# sensor_board.net
KiCad netlist of a schematic drawn in EAGLE
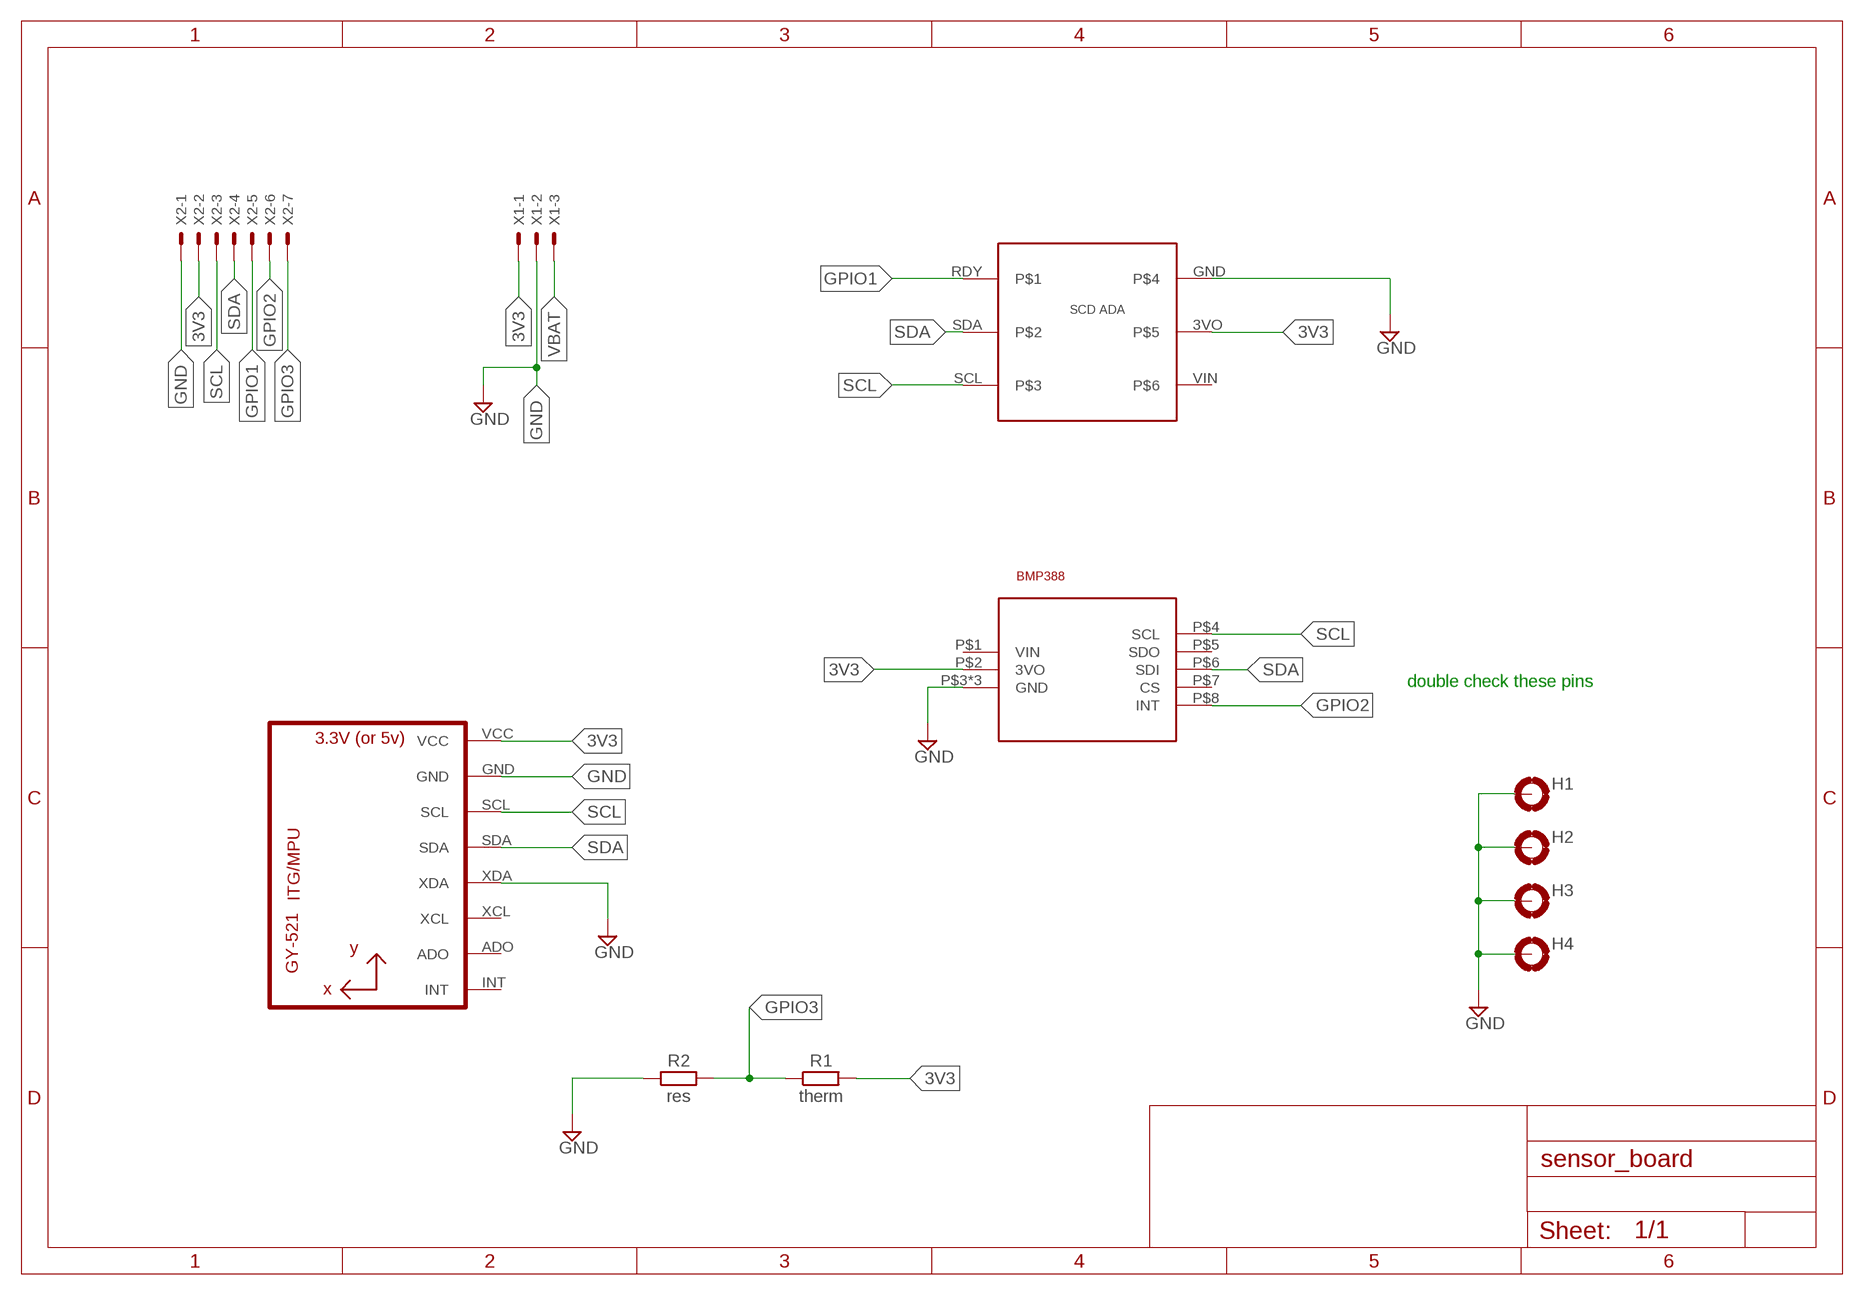
[diagram p0: schematic, sheet 1]

(export (version "E")
  (design (tool "Eeschema 10.0.6"))
  (components
    (comp (ref "H1")
      (value "MOUNT-PAD-ROUND3.0")
      (footprint "eagle-import:3,0-PAD")
      (libsource (lib "eagle-import") (part "MOUNT-PAD-ROUND3.0"))
    )
    (comp (ref "H2")
      (value "MOUNT-PAD-ROUND3.0")
      (footprint "eagle-import:3,0-PAD")
      (libsource (lib "eagle-import") (part "MOUNT-PAD-ROUND3.0"))
    )
    (comp (ref "H3")
      (value "MOUNT-PAD-ROUND3.0")
      (footprint "eagle-import:3,0-PAD")
      (libsource (lib "eagle-import") (part "MOUNT-PAD-ROUND3.0"))
    )
    (comp (ref "H4")
      (value "MOUNT-PAD-ROUND3.0")
      (footprint "eagle-import:3,0-PAD")
      (libsource (lib "eagle-import") (part "MOUNT-PAD-ROUND3.0"))
    )
    (comp (ref "R1")
      (value "therm")
      (footprint "eagle-import:RESAD1176W63L850D250B")
      (libsource (lib "eagle-import") (part "RAXIAL-11.7MM-PITCH_"))
    )
    (comp (ref "R2")
      (value "res")
      (footprint "eagle-import:RESAD1176W63L850D250B")
      (libsource (lib "eagle-import") (part "RAXIAL-11.7MM-PITCH_"))
    )
    (comp (ref "U$1")
      (value "BMP388_QT")
      (footprint "eagle-import:BMP388_QT")
      (libsource (lib "eagle-import") (part "BMP388_QT"))
    )
    (comp (ref "U$6")
      (value "SCD30_ADA")
      (footprint "eagle-import:SCD30_ADA")
      (libsource (lib "eagle-import") (part "SCD30_ADA"))
    )
    (comp (ref "U1")
      (value "GY-521MPU6050")
      (footprint "eagle-import:GY-521")
      (fields (field (name "MF") "GODREAM FORDREAM CO., LIMITED") (field (name "MP") "GY-521"))
      (libsource (lib "eagle-import") (part "GY-521MPU6050"))
    )
    (comp (ref "X1")
      (value "JST-XH-03-PIN")
      (footprint "eagle-import:JST-XH_S3B")
      (libsource (lib "eagle-import") (part "JST-XH-03-PIN"))
    )
    (comp (ref "X2")
      (value "JST-XH-07-PIN")
      (footprint "eagle-import:JST-XH_S7B")
      (libsource (lib "eagle-import") (part "JST-XH-07-PIN"))
    )
  )
  (nets
    (net (code "1") (name "3V3") (class "Default")
      (node (ref "R1") (pin "2") (pinfunction "2_2") (pintype "passive"))
      (node (ref "U$1") (pin "P$2") (pinfunction "3VO_P$2") (pintype "bidirectional"))
      (node (ref "U$6") (pin "3VO") (pinfunction "P$5_3VO") (pintype "bidirectional"))
      (node (ref "U1") (pin "VCC") (pinfunction "VCC_VCC") (pintype "bidirectional"))
      (node (ref "X1") (pin "PIN1") (pinfunction "S_PIN1") (pintype "passive"))
      (node (ref "X2") (pin "PIN2") (pinfunction "S_PIN2") (pintype "passive"))
    )
    (net (code "2") (name "GND") (class "Default")
      (node (ref "H1") (pin "B3,0") (pinfunction "MOUNT_B3,0") (pintype "passive"))
      (node (ref "H2") (pin "B3,0") (pinfunction "MOUNT_B3,0") (pintype "passive"))
      (node (ref "H3") (pin "B3,0") (pinfunction "MOUNT_B3,0") (pintype "passive"))
      (node (ref "H4") (pin "B3,0") (pinfunction "MOUNT_B3,0") (pintype "passive"))
      (node (ref "R2") (pin "1") (pinfunction "1_1") (pintype "passive"))
      (node (ref "U$1") (pin "P$10") (pinfunction "GND_P$10") (pintype "bidirectional"))
      (node (ref "U$1") (pin "P$3") (pinfunction "GND_P$3") (pintype "bidirectional"))
      (node (ref "U$1") (pin "P$9") (pinfunction "GND_P$9") (pintype "bidirectional"))
      (node (ref "U$6") (pin "GND") (pinfunction "P$4_GND") (pintype "bidirectional"))
      (node (ref "U1") (pin "GND") (pinfunction "GND_GND") (pintype "bidirectional"))
      (node (ref "U1") (pin "XDA") (pinfunction "XDA_XDA") (pintype "bidirectional"))
      (node (ref "X1") (pin "PIN2") (pinfunction "S_PIN2") (pintype "passive"))
      (node (ref "X2") (pin "PIN1") (pinfunction "S_PIN1") (pintype "passive"))
    )
    (net (code "3") (name "GPIO1") (class "Default")
      (node (ref "U$6") (pin "RDY") (pinfunction "P$1_RDY") (pintype "bidirectional"))
      (node (ref "X2") (pin "PIN5") (pinfunction "S_PIN5") (pintype "passive"))
    )
    (net (code "4") (name "GPIO2") (class "Default")
      (node (ref "U$1") (pin "P$8") (pinfunction "INT_P$8") (pintype "bidirectional"))
      (node (ref "X2") (pin "PIN6") (pinfunction "S_PIN6") (pintype "passive"))
    )
    (net (code "5") (name "GPIO3") (class "Default")
      (node (ref "R1") (pin "1") (pinfunction "1_1") (pintype "passive"))
      (node (ref "R2") (pin "2") (pinfunction "2_2") (pintype "passive"))
      (node (ref "X2") (pin "PIN7") (pinfunction "S_PIN7") (pintype "passive"))
    )
    (net (code "6") (name "SCL") (class "Default")
      (node (ref "U$1") (pin "P$4") (pinfunction "SCL_P$4") (pintype "bidirectional"))
      (node (ref "U$6") (pin "SCL") (pinfunction "P$3_SCL") (pintype "bidirectional"))
      (node (ref "U1") (pin "SCL") (pinfunction "SCL_SCL") (pintype "bidirectional"))
      (node (ref "X2") (pin "PIN3") (pinfunction "S_PIN3") (pintype "passive"))
    )
    (net (code "7") (name "SDA") (class "Default")
      (node (ref "U$1") (pin "P$6") (pinfunction "SDI_P$6") (pintype "bidirectional"))
      (node (ref "U$6") (pin "SDA") (pinfunction "P$2_SDA") (pintype "bidirectional"))
      (node (ref "U1") (pin "SDA") (pinfunction "SDA_SDA") (pintype "bidirectional"))
      (node (ref "X2") (pin "PIN4") (pinfunction "S_PIN4") (pintype "passive"))
    )
    (net (code "8") (name "VBAT") (class "Default")
      (node (ref "X1") (pin "PIN3") (pinfunction "S_PIN3") (pintype "passive"))
    )
    (net (code "9") (name "unconnected-(U$1-CS-PadP$7)") (class "Default")
      (node (ref "U$1") (pin "P$7") (pinfunction "CS_P$7") (pintype "bidirectional"))
    )
    (net (code "10") (name "unconnected-(U$1-SDO-PadP$5)") (class "Default")
      (node (ref "U$1") (pin "P$5") (pinfunction "SDO_P$5") (pintype "bidirectional"))
    )
    (net (code "11") (name "unconnected-(U$1-VIN-PadP$1)") (class "Default")
      (node (ref "U$1") (pin "P$1") (pinfunction "VIN_P$1") (pintype "bidirectional"))
    )
    (net (code "12") (name "unconnected-(U$6-P$6-PadVIN)") (class "Default")
      (node (ref "U$6") (pin "VIN") (pinfunction "P$6_VIN") (pintype "bidirectional"))
    )
    (net (code "13") (name "unconnected-(U1-PadADO)") (class "Default")
      (node (ref "U1") (pin "ADO") (pinfunction "ADO_ADO") (pintype "bidirectional"))
    )
    (net (code "14") (name "unconnected-(U1-PadINT)") (class "Default")
      (node (ref "U1") (pin "INT") (pinfunction "INT_INT") (pintype "bidirectional"))
    )
    (net (code "15") (name "unconnected-(U1-PadXCL)") (class "Default")
      (node (ref "U1") (pin "XCL") (pinfunction "XCL_XCL") (pintype "bidirectional"))
    )
  )
)
